# Schematic.net
KiCad netlist of a schematic drawn in Altium Designer
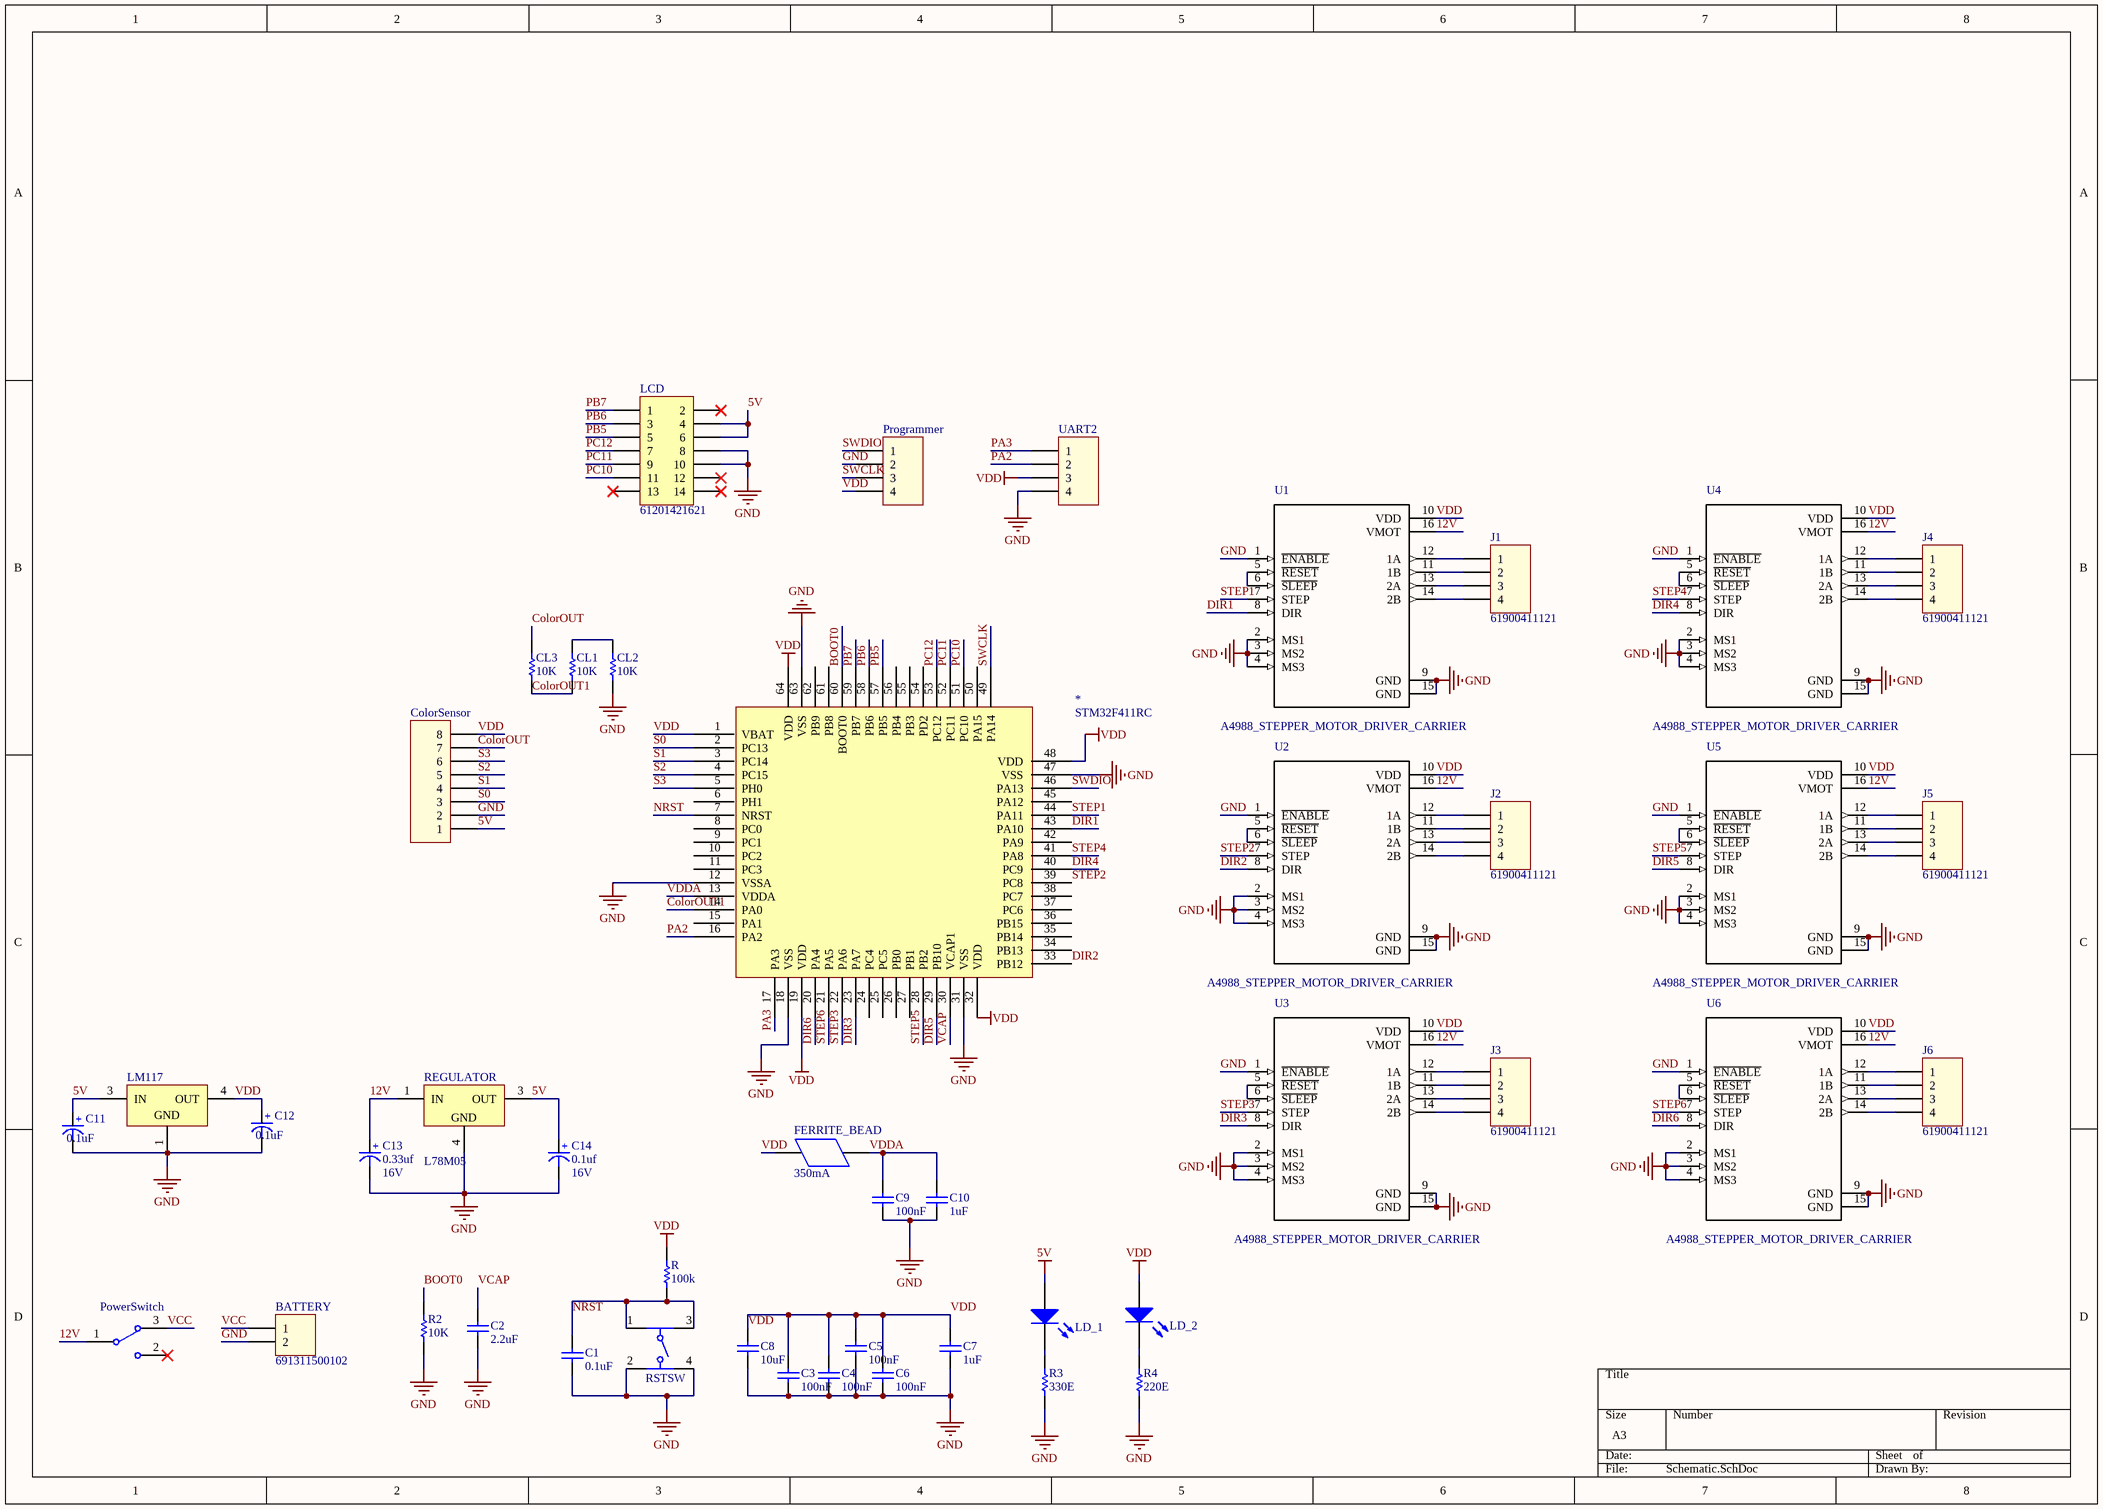
[diagram p0: Schematic.SchDoc]

(export (version "E")
  (design (tool "Eeschema 10.0.6"))
  (components
    (comp (ref "*")
      (value "STM32F411RC")
      (footprint "STM32F411RC_")
      (libsource (lib "STM32F411RCT6_LQFP64_NEW") (part "STM32F411RC"))
    )
    (comp (ref "BATTERY")
      (value "691311500102")
      (footprint "691311500102")
      (description "WR-TBL Serie 311 - 5.08 mm Close Vertical PCB Header, 02p")
      (fields (field (name "PUBLISHER") "Wurth Elektronik"))
      (libsource (lib "Phoenix - Female 5.08mm") (part "691311500102"))
    )
    (comp (ref "C1")
      (value "0.1uF")
      (footprint "CAPC3413X12N")
      (description "CAP 0805")
      (fields (field (name "DESIGNER") "Abbas Basereh"))
      (libsource (lib "Altium") (part "CAP SMD 0805"))
    )
    (comp (ref "C2")
      (value "2.2uF")
      (footprint "CAPC3413X12N")
      (description "CAP 0805")
      (fields (field (name "DESIGNER") "Abbas Basereh"))
      (libsource (lib "Altium") (part "CAP SMD 0805"))
    )
    (comp (ref "C3")
      (value "100nF")
      (footprint "CAPC3413X12N")
      (description "CAP 0805")
      (fields (field (name "DESIGNER") "Abbas Basereh"))
      (libsource (lib "Altium") (part "CAP SMD 0805"))
    )
    (comp (ref "C4")
      (value "100nF")
      (footprint "CAPC3413X12N")
      (description "CAP 0805")
      (fields (field (name "DESIGNER") "Abbas Basereh"))
      (libsource (lib "Altium") (part "CAP SMD 0805"))
    )
    (comp (ref "C5")
      (value "100nF")
      (footprint "CAPC3413X12N")
      (description "CAP 0805")
      (fields (field (name "DESIGNER") "Abbas Basereh"))
      (libsource (lib "Altium") (part "CAP SMD 0805"))
    )
    (comp (ref "C6")
      (value "100nF")
      (footprint "CAPC3413X12N")
      (description "CAP 0805")
      (fields (field (name "DESIGNER") "Abbas Basereh"))
      (libsource (lib "Altium") (part "CAP SMD 0805"))
    )
    (comp (ref "C7")
      (value "1uF")
      (footprint "CAPC3413X12N")
      (description "CAP 0805")
      (fields (field (name "DESIGNER") "Abbas Basereh"))
      (libsource (lib "Altium") (part "CAP SMD 0805"))
    )
    (comp (ref "C8")
      (value "10uF")
      (footprint "CAPC3413X12N")
      (description "CAP 0805")
      (fields (field (name "DESIGNER") "Abbas Basereh"))
      (libsource (lib "Altium") (part "CAP SMD 0805"))
    )
    (comp (ref "C9")
      (value "100nF")
      (footprint "CAPC3413X12N")
      (description "CAP 0805")
      (fields (field (name "DESIGNER") "Abbas Basereh"))
      (libsource (lib "Altium") (part "CAP SMD 0805"))
    )
    (comp (ref "C10")
      (value "1uF")
      (footprint "CAPC3413X12N")
      (description "CAP 0805")
      (fields (field (name "DESIGNER") "Abbas Basereh"))
      (libsource (lib "Altium") (part "CAP SMD 0805"))
    )
    (comp (ref "C11")
      (value "0.1uF")
      (footprint "cap 00")
      (description "Polar Capacitor")
      (fields (field (name "DESIGNER") "Eng. Saeid Jorablo") (field (name "PUBLISHER") "SJ Unlimited"))
      (libsource (lib "Passives") (part "CAP_Polar"))
    )
    (comp (ref "C12")
      (value "0.1uF")
      (footprint "cap 00")
      (description "Polar Capacitor")
      (fields (field (name "DESIGNER") "Eng. Saeid Jorablo") (field (name "PUBLISHER") "SJ Unlimited"))
      (libsource (lib "Passives") (part "CAP_Polar"))
    )
    (comp (ref "C13")
      (value "0.33uf")
      (footprint "cap 01")
      (description "Polar Capacitor")
      (fields
        (field (name "VOLTAGE") "16V")
        (field (name "DESIGNER") "Eng. Saeid Jorablo")
        (field (name "PUBLISHER") "SJ Unlimited")
      )
      (libsource (lib "Passives") (part "CAP_Polar"))
    )
    (comp (ref "C14")
      (value "0.1uf")
      (footprint "cap 01")
      (description "Polar Capacitor")
      (fields
        (field (name "VOLTAGE") "16V")
        (field (name "DESIGNER") "Eng. Saeid Jorablo")
        (field (name "PUBLISHER") "SJ Unlimited")
      )
      (libsource (lib "Passives") (part "CAP_Polar"))
    )
    (comp (ref "CL1")
      (value "10K")
      (footprint "RES0805")
      (description "TOTAL SMD RESISTOR PACK")
      (fields (field (name "DESIGNER") "Abbas Basereh"))
      (libsource (lib "Altium") (part "RES SMD PACKAGE"))
    )
    (comp (ref "CL2")
      (value "10K")
      (footprint "RES0805")
      (description "TOTAL SMD RESISTOR PACK")
      (fields (field (name "DESIGNER") "Abbas Basereh"))
      (libsource (lib "Altium") (part "RES SMD PACKAGE"))
    )
    (comp (ref "CL3")
      (value "10K")
      (footprint "RES0805")
      (description "TOTAL SMD RESISTOR PACK")
      (fields (field (name "DESIGNER") "Abbas Basereh"))
      (libsource (lib "Altium") (part "RES SMD PACKAGE"))
    )
    (comp (ref "ColorSensor")
      (value "~")
      (footprint "61900811121")
      (description "WR-WTB 2.54mm Male Locking Header, 8p")
      (fields (field (name "PART NUMBER") "61900811121") (field (name "PUBLISHER") "Wurth Elektronik"))
      (libsource (lib "Relimate") (part "61900811121"))
    )
    (comp (ref "FERRITE_BEAD")
      (value "350mA")
      (footprint "PassiveComponents:0805 (2012) Capacitor")
      (description "Ferrite Beads")
      (libsource (lib "PassiveComponents") (part "Ferrite Beads"))
    )
    (comp (ref "J1")
      (value "61900411121")
      (footprint "61900411121")
      (description "WR-WTB 2.54mm Male Locking Header, 4p")
      (fields (field (name "PUBLISHER") "Wurth Elektronik"))
      (libsource (lib "Relimate") (part "61900411121"))
    )
    (comp (ref "J2")
      (value "61900411121")
      (footprint "61900411121")
      (description "WR-WTB 2.54mm Male Locking Header, 4p")
      (fields (field (name "PUBLISHER") "Wurth Elektronik"))
      (libsource (lib "Relimate") (part "61900411121"))
    )
    (comp (ref "J3")
      (value "61900411121")
      (footprint "61900411121")
      (description "WR-WTB 2.54mm Male Locking Header, 4p")
      (fields (field (name "PUBLISHER") "Wurth Elektronik"))
      (libsource (lib "Relimate") (part "61900411121"))
    )
    (comp (ref "J4")
      (value "61900411121")
      (footprint "61900411121")
      (description "WR-WTB 2.54mm Male Locking Header, 4p")
      (fields (field (name "PUBLISHER") "Wurth Elektronik"))
      (libsource (lib "Relimate") (part "61900411121"))
    )
    (comp (ref "J5")
      (value "61900411121")
      (footprint "61900411121")
      (description "WR-WTB 2.54mm Male Locking Header, 4p")
      (fields (field (name "PUBLISHER") "Wurth Elektronik"))
      (libsource (lib "Relimate") (part "61900411121"))
    )
    (comp (ref "J6")
      (value "61900411121")
      (footprint "61900411121")
      (description "WR-WTB 2.54mm Male Locking Header, 4p")
      (fields (field (name "PUBLISHER") "Wurth Elektronik"))
      (libsource (lib "Relimate") (part "61900411121"))
    )
    (comp (ref "LCD")
      (value "61201421621")
      (footprint "61201421621")
      (description "WR-BHD 2.54mm Male Box Header")
      (fields (field (name "MANUFACTURER") "Wurth Elektronik") (field (name "CREATED BY") "Baojun Chen"))
      (libsource (lib "FRC Base") (part "61201421621"))
    )
    (comp (ref "LD_1")
      (value "SMD 1206 LED")
      (footprint "LED-3mm")
      (description "Typical LED")
      (libsource (lib "AbbasBasereh09365731239") (part "LED 3mm"))
    )
    (comp (ref "LD_2")
      (value "SMD 1206 LED")
      (footprint "LED-3mm")
      (description "Typical LED")
      (libsource (lib "AbbasBasereh09365731239") (part "LED 3mm"))
    )
    (comp (ref "LM117")
      (value "~")
      (footprint "SOT223_N")
      (description "x.x Volt, 800mA Low-Dropout Linear Regulator, 3-pin TO-252")
      (fields
        (field (name "PARTNUMBER") "LM1117DT-3.3")
        (field (name "MANUFACTURER") "National Semiconductor")
      )
      (libsource (lib "Altium") (part "LM1117DT-x.x"))
    )
    (comp (ref "PowerSwitch")
      (value "450301014042")
      (footprint "450301014042")
      (description "WS-SLTV 10x2.5 mm THT")
      (fields (field (name "PUBLISHER") "Wurth Elektronik"))
      (libsource (lib "Switch - SlideSwitch RED") (part "450301014042"))
    )
    (comp (ref "Programmer")
      (value "~")
      (footprint "61900411121")
      (description "WR-WTB 2.54mm Male Locking Header, 4p")
      (fields (field (name "PART NUMBER") "61900411121") (field (name "PUBLISHER") "Wurth Elektronik"))
      (libsource (lib "Relimate") (part "61900411121"))
    )
    (comp (ref "R")
      (value "100k")
      (footprint "RES0805")
      (description "TOTAL SMD RESISTOR PACK")
      (fields (field (name "DESIGNER") "Abbas Basereh"))
      (libsource (lib "Altium") (part "RES SMD PACKAGE"))
    )
    (comp (ref "R2")
      (value "10K")
      (footprint "RES0805")
      (description "TOTAL SMD RESISTOR PACK")
      (fields (field (name "DESIGNER") "Abbas Basereh"))
      (libsource (lib "Altium") (part "RES SMD PACKAGE"))
    )
    (comp (ref "R3")
      (value "330E")
      (footprint "RES0805")
      (description "TOTAL SMD RESISTOR PACK")
      (fields (field (name "DESIGNER") "Abbas Basereh"))
      (libsource (lib "Altium") (part "RES SMD PACKAGE"))
    )
    (comp (ref "R4")
      (value "220E")
      (footprint "RES0805")
      (description "TOTAL SMD RESISTOR PACK")
      (fields (field (name "DESIGNER") "Abbas Basereh"))
      (libsource (lib "Altium") (part "RES SMD PACKAGE"))
    )
    (comp (ref "REGULATOR")
      (value "L78M05")
      (footprint "TO-252")
      (description "Precision 500mA Regulator")
      (libsource (lib "Altium") (part "L78M05"))
    )
    (comp (ref "RSTSW")
      (value "430156050736")
      (footprint "4301x60507x6_6x6x5")
      (description "WS-TATV 6x6mm Tact Switch, THT version")
      (fields (field (name "PUBLISHER") "Wurth Elektronik"))
      (libsource (lib "Switch - Tactile") (part "430156050736"))
    )
    (comp (ref "U1")
      (value "A4988_STEPPER_MOTOR_DRIVER_CARRIER")
      (footprint "*MODULE_A4988_STEPPER_MOTOR_DRIVER_CARRIER")
      (description "Stepper Motor Driver")
      (fields (field (name "MF") "Pololu") (field (name "MP") "A4988 STEPPER MOTOR DRIVER CARRIER"))
      (libsource (lib "A4988_STEPPER_MOTOR_DRIVER_CARRIER") (part "A4988_STEPPER_MOTOR_DRIVER_CARRIER"))
    )
    (comp (ref "U2")
      (value "A4988_STEPPER_MOTOR_DRIVER_CARRIER")
      (footprint "*MODULE_A4988_STEPPER_MOTOR_DRIVER_CARRIER")
      (description "Stepper Motor Driver")
      (fields (field (name "MF") "Pololu") (field (name "MP") "A4988 STEPPER MOTOR DRIVER CARRIER"))
      (libsource (lib "A4988_STEPPER_MOTOR_DRIVER_CARRIER") (part "A4988_STEPPER_MOTOR_DRIVER_CARRIER"))
    )
    (comp (ref "U3")
      (value "A4988_STEPPER_MOTOR_DRIVER_CARRIER")
      (footprint "*MODULE_A4988_STEPPER_MOTOR_DRIVER_CARRIER")
      (description "Stepper Motor Driver")
      (fields (field (name "MF") "Pololu") (field (name "MP") "A4988 STEPPER MOTOR DRIVER CARRIER"))
      (libsource (lib "A4988_STEPPER_MOTOR_DRIVER_CARRIER") (part "A4988_STEPPER_MOTOR_DRIVER_CARRIER"))
    )
    (comp (ref "U4")
      (value "A4988_STEPPER_MOTOR_DRIVER_CARRIER")
      (footprint "*MODULE_A4988_STEPPER_MOTOR_DRIVER_CARRIER")
      (description "Stepper Motor Driver")
      (fields (field (name "MF") "Pololu") (field (name "MP") "A4988 STEPPER MOTOR DRIVER CARRIER"))
      (libsource (lib "A4988_STEPPER_MOTOR_DRIVER_CARRIER") (part "A4988_STEPPER_MOTOR_DRIVER_CARRIER"))
    )
    (comp (ref "U5")
      (value "A4988_STEPPER_MOTOR_DRIVER_CARRIER")
      (footprint "*MODULE_A4988_STEPPER_MOTOR_DRIVER_CARRIER")
      (description "Stepper Motor Driver")
      (fields (field (name "MF") "Pololu") (field (name "MP") "A4988 STEPPER MOTOR DRIVER CARRIER"))
      (libsource (lib "A4988_STEPPER_MOTOR_DRIVER_CARRIER") (part "A4988_STEPPER_MOTOR_DRIVER_CARRIER"))
    )
    (comp (ref "U6")
      (value "A4988_STEPPER_MOTOR_DRIVER_CARRIER")
      (footprint "*MODULE_A4988_STEPPER_MOTOR_DRIVER_CARRIER")
      (description "Stepper Motor Driver")
      (fields (field (name "MF") "Pololu") (field (name "MP") "A4988 STEPPER MOTOR DRIVER CARRIER"))
      (libsource (lib "A4988_STEPPER_MOTOR_DRIVER_CARRIER") (part "A4988_STEPPER_MOTOR_DRIVER_CARRIER"))
    )
    (comp (ref "UART2")
      (value "~")
      (footprint "61900411121")
      (description "WR-WTB 2.54mm Male Locking Header, 4p")
      (fields (field (name "PART NUMBER") "61900411121") (field (name "PUBLISHER") "Wurth Elektronik"))
      (libsource (lib "Relimate") (part "61900411121"))
    )
  )
  (nets
    (net (code "1") (name "/12V") (class "Default")
      (node (ref "C13") (pin "1") (pinfunction "+_1") (pintype "passive"))
      (node (ref "PowerSwitch") (pin "1") (pinfunction "COM_1") (pintype "passive"))
      (node (ref "REGULATOR") (pin "1") (pinfunction "IN_1") (pintype "power_in"))
      (node (ref "U1") (pin "16") (pinfunction "VMOT_16") (pintype "power_in"))
      (node (ref "U2") (pin "16") (pinfunction "VMOT_16") (pintype "power_in"))
      (node (ref "U3") (pin "16") (pinfunction "VMOT_16") (pintype "power_in"))
      (node (ref "U4") (pin "16") (pinfunction "VMOT_16") (pintype "power_in"))
      (node (ref "U5") (pin "16") (pinfunction "VMOT_16") (pintype "power_in"))
      (node (ref "U6") (pin "16") (pinfunction "VMOT_16") (pintype "power_in"))
    )
    (net (code "2") (name "/BOOT0") (class "Default")
      (node (ref "*") (pin "60") (pinfunction "BOOT0_60") (pintype "passive"))
      (node (ref "R2") (pin "2") (pinfunction "2_2") (pintype "passive"))
    )
    (net (code "3") (name "/ColorOUT") (class "Default")
      (node (ref "CL3") (pin "2") (pinfunction "2_2") (pintype "passive"))
      (node (ref "ColorSensor") (pin "7") (pinfunction "7_7") (pintype "passive"))
    )
    (net (code "4") (name "/ColorOUT1") (class "Default")
      (node (ref "*") (pin "14") (pinfunction "PA0_14") (pintype "passive"))
      (node (ref "CL1") (pin "1") (pinfunction "1_1") (pintype "passive"))
      (node (ref "CL3") (pin "1") (pinfunction "1_1") (pintype "passive"))
    )
    (net (code "5") (name "/DIR1") (class "Default")
      (node (ref "*") (pin "43") (pinfunction "PA10_43") (pintype "passive"))
      (node (ref "U1") (pin "8") (pinfunction "DIR_8") (pintype "input"))
    )
    (net (code "6") (name "/DIR2") (class "Default")
      (node (ref "*") (pin "33") (pinfunction "PB12_33") (pintype "passive"))
      (node (ref "U2") (pin "8") (pinfunction "DIR_8") (pintype "input"))
    )
    (net (code "7") (name "/DIR3") (class "Default")
      (node (ref "*") (pin "23") (pinfunction "PA7_23") (pintype "passive"))
      (node (ref "U3") (pin "8") (pinfunction "DIR_8") (pintype "input"))
    )
    (net (code "8") (name "/DIR4") (class "Default")
      (node (ref "*") (pin "40") (pinfunction "PC9_40") (pintype "passive"))
      (node (ref "U4") (pin "8") (pinfunction "DIR_8") (pintype "input"))
    )
    (net (code "9") (name "/DIR5") (class "Default")
      (node (ref "*") (pin "29") (pinfunction "PB10_29") (pintype "passive"))
      (node (ref "U5") (pin "8") (pinfunction "DIR_8") (pintype "input"))
    )
    (net (code "10") (name "/DIR6") (class "Default")
      (node (ref "*") (pin "20") (pinfunction "PA4_20") (pintype "passive"))
      (node (ref "U6") (pin "8") (pinfunction "DIR_8") (pintype "input"))
    )
    (net (code "11") (name "/NRST") (class "Default")
      (node (ref "*") (pin "7") (pinfunction "NRST_7") (pintype "passive"))
      (node (ref "C1") (pin "1") (pinfunction "1_1") (pintype "passive"))
      (node (ref "R") (pin "1") (pinfunction "1_1") (pintype "passive"))
      (node (ref "RSTSW") (pin "1") (pinfunction "1_1") (pintype "passive"))
      (node (ref "RSTSW") (pin "3") (pinfunction "3_3") (pintype "passive"))
    )
    (net (code "12") (name "/PA2") (class "Default")
      (node (ref "*") (pin "16") (pinfunction "PA2_16") (pintype "passive"))
      (node (ref "UART2") (pin "2") (pinfunction "2_2") (pintype "passive"))
    )
    (net (code "13") (name "/PA3") (class "Default")
      (node (ref "*") (pin "17") (pinfunction "PA3_17") (pintype "passive"))
      (node (ref "UART2") (pin "1") (pinfunction "1_1") (pintype "passive"))
    )
    (net (code "14") (name "/PB5") (class "Default")
      (node (ref "*") (pin "57") (pinfunction "PB5_57") (pintype "passive"))
      (node (ref "LCD") (pin "5") (pinfunction "5_5") (pintype "passive"))
    )
    (net (code "15") (name "/PB6") (class "Default")
      (node (ref "*") (pin "58") (pinfunction "PB6_58") (pintype "passive"))
      (node (ref "LCD") (pin "3") (pinfunction "3_3") (pintype "passive"))
    )
    (net (code "16") (name "/PB7") (class "Default")
      (node (ref "*") (pin "59") (pinfunction "PB7_59") (pintype "passive"))
      (node (ref "LCD") (pin "1") (pinfunction "1_1") (pintype "passive"))
    )
    (net (code "17") (name "/PC10") (class "Default")
      (node (ref "*") (pin "51") (pinfunction "PC10_51") (pintype "passive"))
      (node (ref "LCD") (pin "11") (pinfunction "11_11") (pintype "passive"))
    )
    (net (code "18") (name "/PC11") (class "Default")
      (node (ref "*") (pin "52") (pinfunction "PC11_52") (pintype "passive"))
      (node (ref "LCD") (pin "9") (pinfunction "9_9") (pintype "passive"))
    )
    (net (code "19") (name "/PC12") (class "Default")
      (node (ref "*") (pin "53") (pinfunction "PC12_53") (pintype "passive"))
      (node (ref "LCD") (pin "7") (pinfunction "7_7") (pintype "passive"))
    )
    (net (code "20") (name "/S0") (class "Default")
      (node (ref "*") (pin "2") (pinfunction "PC13_2") (pintype "passive"))
      (node (ref "ColorSensor") (pin "3") (pinfunction "3_3") (pintype "passive"))
    )
    (net (code "21") (name "/S1") (class "Default")
      (node (ref "*") (pin "3") (pinfunction "PC14_3") (pintype "passive"))
      (node (ref "ColorSensor") (pin "4") (pinfunction "4_4") (pintype "passive"))
    )
    (net (code "22") (name "/S2") (class "Default")
      (node (ref "*") (pin "4") (pinfunction "PC15_4") (pintype "passive"))
      (node (ref "ColorSensor") (pin "5") (pinfunction "5_5") (pintype "passive"))
    )
    (net (code "23") (name "/S3") (class "Default")
      (node (ref "*") (pin "5") (pinfunction "PH0_5") (pintype "passive"))
      (node (ref "ColorSensor") (pin "6") (pinfunction "6_6") (pintype "passive"))
    )
    (net (code "24") (name "/STEP1") (class "Default")
      (node (ref "*") (pin "44") (pinfunction "PA11_44") (pintype "passive"))
      (node (ref "U1") (pin "7") (pinfunction "STEP_7") (pintype "input"))
    )
    (net (code "25") (name "/STEP2") (class "Default")
      (node (ref "*") (pin "39") (pinfunction "PC8_39") (pintype "passive"))
      (node (ref "U2") (pin "7") (pinfunction "STEP_7") (pintype "input"))
    )
    (net (code "26") (name "/STEP3") (class "Default")
      (node (ref "*") (pin "22") (pinfunction "PA6_22") (pintype "passive"))
      (node (ref "U3") (pin "7") (pinfunction "STEP_7") (pintype "input"))
    )
    (net (code "27") (name "/STEP4") (class "Default")
      (node (ref "*") (pin "41") (pinfunction "PA8_41") (pintype "passive"))
      (node (ref "U4") (pin "7") (pinfunction "STEP_7") (pintype "input"))
    )
    (net (code "28") (name "/STEP5") (class "Default")
      (node (ref "*") (pin "28") (pinfunction "PB2_28") (pintype "passive"))
      (node (ref "U5") (pin "7") (pinfunction "STEP_7") (pintype "input"))
    )
    (net (code "29") (name "/STEP6") (class "Default")
      (node (ref "*") (pin "21") (pinfunction "PA5_21") (pintype "passive"))
      (node (ref "U6") (pin "7") (pinfunction "STEP_7") (pintype "input"))
    )
    (net (code "30") (name "/SWCLK") (class "Default")
      (node (ref "*") (pin "49") (pinfunction "PA14_49") (pintype "passive"))
      (node (ref "Programmer") (pin "3") (pinfunction "3_3") (pintype "passive"))
    )
    (net (code "31") (name "/SWDIO") (class "Default")
      (node (ref "*") (pin "46") (pinfunction "PA13_46") (pintype "passive"))
      (node (ref "Programmer") (pin "1") (pinfunction "1_1") (pintype "passive"))
    )
    (net (code "32") (name "/VCAP") (class "Default")
      (node (ref "*") (pin "30") (pinfunction "VCAP1_30") (pintype "passive"))
      (node (ref "C2") (pin "1") (pinfunction "1_1") (pintype "passive"))
    )
    (net (code "33") (name "/VCC") (class "Default")
      (node (ref "BATTERY") (pin "1") (pinfunction "1_1") (pintype "passive"))
      (node (ref "PowerSwitch") (pin "3") (pinfunction "3_3") (pintype "passive"))
    )
    (net (code "34") (name "/VDDA") (class "Default")
      (node (ref "*") (pin "13") (pinfunction "VDDA_13") (pintype "passive"))
      (node (ref "C10") (pin "2") (pinfunction "2_2") (pintype "passive"))
      (node (ref "C9") (pin "2") (pinfunction "2_2") (pintype "passive"))
      (node (ref "FERRITE_BEAD") (pin "1") (pinfunction "1_1") (pintype "passive"))
    )
    (net (code "35") (name "5V") (class "Default")
      (node (ref "C11") (pin "1") (pinfunction "+_1") (pintype "passive"))
      (node (ref "C14") (pin "1") (pinfunction "+_1") (pintype "passive"))
      (node (ref "ColorSensor") (pin "1") (pinfunction "1_1") (pintype "passive"))
      (node (ref "LCD") (pin "4") (pinfunction "4_4") (pintype "passive"))
      (node (ref "LCD") (pin "6") (pinfunction "6_6") (pintype "passive"))
      (node (ref "LD_1") (pin "1") (pinfunction "A_1") (pintype "passive"))
      (node (ref "LM117") (pin "3") (pinfunction "IN_3") (pintype "power_in"))
      (node (ref "REGULATOR") (pin "3") (pinfunction "OUT_3") (pintype "power_in"))
    )
    (net (code "36") (name "GND") (class "Default")
      (node (ref "*") (pin "12") (pinfunction "VSSA_12") (pintype "passive"))
      (node (ref "*") (pin "18") (pinfunction "VSS_18") (pintype "passive"))
      (node (ref "*") (pin "31") (pinfunction "VSS_31") (pintype "passive"))
      (node (ref "*") (pin "47") (pinfunction "VSS_47") (pintype "passive"))
      (node (ref "*") (pin "63") (pinfunction "VSS_63") (pintype "passive"))
      (node (ref "BATTERY") (pin "2") (pinfunction "2_2") (pintype "passive"))
      (node (ref "C1") (pin "2") (pinfunction "2_2") (pintype "passive"))
      (node (ref "C10") (pin "1") (pinfunction "1_1") (pintype "passive"))
      (node (ref "C11") (pin "2") (pinfunction "-_2") (pintype "passive"))
      (node (ref "C12") (pin "2") (pinfunction "-_2") (pintype "passive"))
      (node (ref "C13") (pin "2") (pinfunction "-_2") (pintype "passive"))
      (node (ref "C14") (pin "2") (pinfunction "-_2") (pintype "passive"))
      (node (ref "C2") (pin "2") (pinfunction "2_2") (pintype "passive"))
      (node (ref "C3") (pin "1") (pinfunction "1_1") (pintype "passive"))
      (node (ref "C4") (pin "1") (pinfunction "1_1") (pintype "passive"))
      (node (ref "C5") (pin "1") (pinfunction "1_1") (pintype "passive"))
      (node (ref "C6") (pin "1") (pinfunction "1_1") (pintype "passive"))
      (node (ref "C7") (pin "1") (pinfunction "1_1") (pintype "passive"))
      (node (ref "C8") (pin "1") (pinfunction "1_1") (pintype "passive"))
      (node (ref "C9") (pin "1") (pinfunction "1_1") (pintype "passive"))
      (node (ref "CL2") (pin "1") (pinfunction "1_1") (pintype "passive"))
      (node (ref "ColorSensor") (pin "2") (pinfunction "2_2") (pintype "passive"))
      (node (ref "LCD") (pin "10") (pinfunction "10_10") (pintype "passive"))
      (node (ref "LCD") (pin "8") (pinfunction "8_8") (pintype "passive"))
      (node (ref "LM117") (pin "1") (pinfunction "GND_1") (pintype "power_in"))
      (node (ref "Programmer") (pin "2") (pinfunction "2_2") (pintype "passive"))
      (node (ref "R2") (pin "1") (pinfunction "1_1") (pintype "passive"))
      (node (ref "R3") (pin "1") (pinfunction "1_1") (pintype "passive"))
      (node (ref "R4") (pin "1") (pinfunction "1_1") (pintype "passive"))
      (node (ref "REGULATOR") (pin "4") (pinfunction "GND_4") (pintype "power_in"))
      (node (ref "RSTSW") (pin "2") (pinfunction "2_2") (pintype "passive"))
      (node (ref "RSTSW") (pin "4") (pinfunction "4_4") (pintype "passive"))
      (node (ref "U1") (pin "1") (pinfunction "~{ENABLE}_1") (pintype "input"))
      (node (ref "U1") (pin "15") (pinfunction "GND_15") (pintype "power_in"))
      (node (ref "U1") (pin "2") (pinfunction "MS1_2") (pintype "input"))
      (node (ref "U1") (pin "3") (pinfunction "MS2_3") (pintype "input"))
      (node (ref "U1") (pin "4") (pinfunction "MS3_4") (pintype "input"))
      (node (ref "U1") (pin "9") (pinfunction "GND_9") (pintype "power_in"))
      (node (ref "U2") (pin "1") (pinfunction "~{ENABLE}_1") (pintype "input"))
      (node (ref "U2") (pin "15") (pinfunction "GND_15") (pintype "power_in"))
      (node (ref "U2") (pin "2") (pinfunction "MS1_2") (pintype "input"))
      (node (ref "U2") (pin "3") (pinfunction "MS2_3") (pintype "input"))
      (node (ref "U2") (pin "4") (pinfunction "MS3_4") (pintype "input"))
      (node (ref "U2") (pin "9") (pinfunction "GND_9") (pintype "power_in"))
      (node (ref "U3") (pin "1") (pinfunction "~{ENABLE}_1") (pintype "input"))
      (node (ref "U3") (pin "15") (pinfunction "GND_15") (pintype "power_in"))
      (node (ref "U3") (pin "2") (pinfunction "MS1_2") (pintype "input"))
      (node (ref "U3") (pin "3") (pinfunction "MS2_3") (pintype "input"))
      (node (ref "U3") (pin "4") (pinfunction "MS3_4") (pintype "input"))
      (node (ref "U3") (pin "9") (pinfunction "GND_9") (pintype "power_in"))
      (node (ref "U4") (pin "1") (pinfunction "~{ENABLE}_1") (pintype "input"))
      (node (ref "U4") (pin "15") (pinfunction "GND_15") (pintype "power_in"))
      (node (ref "U4") (pin "2") (pinfunction "MS1_2") (pintype "input"))
      (node (ref "U4") (pin "3") (pinfunction "MS2_3") (pintype "input"))
      (node (ref "U4") (pin "4") (pinfunction "MS3_4") (pintype "input"))
      (node (ref "U4") (pin "9") (pinfunction "GND_9") (pintype "power_in"))
      (node (ref "U5") (pin "1") (pinfunction "~{ENABLE}_1") (pintype "input"))
      (node (ref "U5") (pin "15") (pinfunction "GND_15") (pintype "power_in"))
      (node (ref "U5") (pin "2") (pinfunction "MS1_2") (pintype "input"))
      (node (ref "U5") (pin "3") (pinfunction "MS2_3") (pintype "input"))
      (node (ref "U5") (pin "4") (pinfunction "MS3_4") (pintype "input"))
      (node (ref "U5") (pin "9") (pinfunction "GND_9") (pintype "power_in"))
      (node (ref "U6") (pin "1") (pinfunction "~{ENABLE}_1") (pintype "input"))
      (node (ref "U6") (pin "15") (pinfunction "GND_15") (pintype "power_in"))
      (node (ref "U6") (pin "2") (pinfunction "MS1_2") (pintype "input"))
      (node (ref "U6") (pin "3") (pinfunction "MS2_3") (pintype "input"))
      (node (ref "U6") (pin "4") (pinfunction "MS3_4") (pintype "input"))
      (node (ref "U6") (pin "9") (pinfunction "GND_9") (pintype "power_in"))
      (node (ref "UART2") (pin "4") (pinfunction "4_4") (pintype "passive"))
    )
    (net (code "37") (name "Net-(CL1-Pad2)") (class "Default")
      (node (ref "CL1") (pin "2") (pinfunction "2_2") (pintype "passive"))
      (node (ref "CL2") (pin "2") (pinfunction "2_2") (pintype "passive"))
    )
    (net (code "38") (name "Net-(LD_1-K)") (class "Default")
      (node (ref "LD_1") (pin "2") (pinfunction "K_2") (pintype "passive"))
      (node (ref "R3") (pin "2") (pinfunction "2_2") (pintype "passive"))
    )
    (net (code "39") (name "Net-(LD_2-K)") (class "Default")
      (node (ref "LD_2") (pin "2") (pinfunction "K_2") (pintype "passive"))
      (node (ref "R4") (pin "2") (pinfunction "2_2") (pintype "passive"))
    )
    (net (code "40") (name "Net-(U1-1A)") (class "Default")
      (node (ref "J1") (pin "1") (pinfunction "1_1") (pintype "passive"))
      (node (ref "U1") (pin "12") (pinfunction "1A_12") (pintype "output"))
    )
    (net (code "41") (name "Net-(U1-1B)") (class "Default")
      (node (ref "J1") (pin "2") (pinfunction "2_2") (pintype "passive"))
      (node (ref "U1") (pin "11") (pinfunction "1B_11") (pintype "output"))
    )
    (net (code "42") (name "Net-(U1-2A)") (class "Default")
      (node (ref "J1") (pin "3") (pinfunction "3_3") (pintype "passive"))
      (node (ref "U1") (pin "13") (pinfunction "2A_13") (pintype "output"))
    )
    (net (code "43") (name "Net-(U1-2B)") (class "Default")
      (node (ref "J1") (pin "4") (pinfunction "4_4") (pintype "passive"))
      (node (ref "U1") (pin "14") (pinfunction "2B_14") (pintype "output"))
    )
    (net (code "44") (name "Net-(U1-~{RESET})") (class "Default")
      (node (ref "U1") (pin "5") (pinfunction "~{RESET}_5") (pintype "input"))
      (node (ref "U1") (pin "6") (pinfunction "~{SLEEP}_6") (pintype "input"))
    )
    (net (code "45") (name "Net-(U2-1A)") (class "Default")
      (node (ref "J2") (pin "1") (pinfunction "1_1") (pintype "passive"))
      (node (ref "U2") (pin "12") (pinfunction "1A_12") (pintype "output"))
    )
    (net (code "46") (name "Net-(U2-1B)") (class "Default")
      (node (ref "J2") (pin "2") (pinfunction "2_2") (pintype "passive"))
      (node (ref "U2") (pin "11") (pinfunction "1B_11") (pintype "output"))
    )
    (net (code "47") (name "Net-(U2-2A)") (class "Default")
      (node (ref "J2") (pin "3") (pinfunction "3_3") (pintype "passive"))
      (node (ref "U2") (pin "13") (pinfunction "2A_13") (pintype "output"))
    )
    (net (code "48") (name "Net-(U2-2B)") (class "Default")
      (node (ref "J2") (pin "4") (pinfunction "4_4") (pintype "passive"))
      (node (ref "U2") (pin "14") (pinfunction "2B_14") (pintype "output"))
    )
    (net (code "49") (name "Net-(U2-~{RESET})") (class "Default")
      (node (ref "U2") (pin "5") (pinfunction "~{RESET}_5") (pintype "input"))
      (node (ref "U2") (pin "6") (pinfunction "~{SLEEP}_6") (pintype "input"))
    )
    (net (code "50") (name "Net-(U3-1A)") (class "Default")
      (node (ref "J3") (pin "1") (pinfunction "1_1") (pintype "passive"))
      (node (ref "U3") (pin "12") (pinfunction "1A_12") (pintype "output"))
    )
    (net (code "51") (name "Net-(U3-1B)") (class "Default")
      (node (ref "J3") (pin "2") (pinfunction "2_2") (pintype "passive"))
      (node (ref "U3") (pin "11") (pinfunction "1B_11") (pintype "output"))
    )
    (net (code "52") (name "Net-(U3-2A)") (class "Default")
      (node (ref "J3") (pin "3") (pinfunction "3_3") (pintype "passive"))
      (node (ref "U3") (pin "13") (pinfunction "2A_13") (pintype "output"))
    )
    (net (code "53") (name "Net-(U3-2B)") (class "Default")
      (node (ref "J3") (pin "4") (pinfunction "4_4") (pintype "passive"))
      (node (ref "U3") (pin "14") (pinfunction "2B_14") (pintype "output"))
    )
    (net (code "54") (name "Net-(U3-~{RESET})") (class "Default")
      (node (ref "U3") (pin "5") (pinfunction "~{RESET}_5") (pintype "input"))
      (node (ref "U3") (pin "6") (pinfunction "~{SLEEP}_6") (pintype "input"))
    )
    (net (code "55") (name "Net-(U4-1A)") (class "Default")
      (node (ref "J4") (pin "1") (pinfunction "1_1") (pintype "passive"))
      (node (ref "U4") (pin "12") (pinfunction "1A_12") (pintype "output"))
    )
    (net (code "56") (name "Net-(U4-1B)") (class "Default")
      (node (ref "J4") (pin "2") (pinfunction "2_2") (pintype "passive"))
      (node (ref "U4") (pin "11") (pinfunction "1B_11") (pintype "output"))
    )
    (net (code "57") (name "Net-(U4-2A)") (class "Default")
      (node (ref "J4") (pin "3") (pinfunction "3_3") (pintype "passive"))
      (node (ref "U4") (pin "13") (pinfunction "2A_13") (pintype "output"))
    )
    (net (code "58") (name "Net-(U4-2B)") (class "Default")
      (node (ref "J4") (pin "4") (pinfunction "4_4") (pintype "passive"))
      (node (ref "U4") (pin "14") (pinfunction "2B_14") (pintype "output"))
    )
    (net (code "59") (name "Net-(U4-~{RESET})") (class "Default")
      (node (ref "U4") (pin "5") (pinfunction "~{RESET}_5") (pintype "input"))
      (node (ref "U4") (pin "6") (pinfunction "~{SLEEP}_6") (pintype "input"))
    )
    (net (code "60") (name "Net-(U5-1A)") (class "Default")
      (node (ref "J5") (pin "1") (pinfunction "1_1") (pintype "passive"))
      (node (ref "U5") (pin "12") (pinfunction "1A_12") (pintype "output"))
    )
    (net (code "61") (name "Net-(U5-1B)") (class "Default")
      (node (ref "J5") (pin "2") (pinfunction "2_2") (pintype "passive"))
      (node (ref "U5") (pin "11") (pinfunction "1B_11") (pintype "output"))
    )
    (net (code "62") (name "Net-(U5-2A)") (class "Default")
      (node (ref "J5") (pin "3") (pinfunction "3_3") (pintype "passive"))
      (node (ref "U5") (pin "13") (pinfunction "2A_13") (pintype "output"))
    )
    (net (code "63") (name "Net-(U5-2B)") (class "Default")
      (node (ref "J5") (pin "4") (pinfunction "4_4") (pintype "passive"))
      (node (ref "U5") (pin "14") (pinfunction "2B_14") (pintype "output"))
    )
    (net (code "64") (name "Net-(U5-~{RESET})") (class "Default")
      (node (ref "U5") (pin "5") (pinfunction "~{RESET}_5") (pintype "input"))
      (node (ref "U5") (pin "6") (pinfunction "~{SLEEP}_6") (pintype "input"))
    )
    (net (code "65") (name "Net-(U6-1A)") (class "Default")
      (node (ref "J6") (pin "1") (pinfunction "1_1") (pintype "passive"))
      (node (ref "U6") (pin "12") (pinfunction "1A_12") (pintype "output"))
    )
    (net (code "66") (name "Net-(U6-1B)") (class "Default")
      (node (ref "J6") (pin "2") (pinfunction "2_2") (pintype "passive"))
      (node (ref "U6") (pin "11") (pinfunction "1B_11") (pintype "output"))
    )
    (net (code "67") (name "Net-(U6-2A)") (class "Default")
      (node (ref "J6") (pin "3") (pinfunction "3_3") (pintype "passive"))
      (node (ref "U6") (pin "13") (pinfunction "2A_13") (pintype "output"))
    )
    (net (code "68") (name "Net-(U6-2B)") (class "Default")
      (node (ref "J6") (pin "4") (pinfunction "4_4") (pintype "passive"))
      (node (ref "U6") (pin "14") (pinfunction "2B_14") (pintype "output"))
    )
    (net (code "69") (name "Net-(U6-~{RESET})") (class "Default")
      (node (ref "U6") (pin "5") (pinfunction "~{RESET}_5") (pintype "input"))
      (node (ref "U6") (pin "6") (pinfunction "~{SLEEP}_6") (pintype "input"))
    )
    (net (code "70") (name "VDD") (class "Default")
      (node (ref "*") (pin "1") (pinfunction "VBAT_1") (pintype "passive"))
      (node (ref "*") (pin "19") (pinfunction "VDD_19") (pintype "passive"))
      (node (ref "*") (pin "32") (pinfunction "VDD_32") (pintype "passive"))
      (node (ref "*") (pin "48") (pinfunction "VDD_48") (pintype "passive"))
      (node (ref "*") (pin "64") (pinfunction "VDD_64") (pintype "passive"))
      (node (ref "C12") (pin "1") (pinfunction "+_1") (pintype "passive"))
      (node (ref "C3") (pin "2") (pinfunction "2_2") (pintype "passive"))
      (node (ref "C4") (pin "2") (pinfunction "2_2") (pintype "passive"))
      (node (ref "C5") (pin "2") (pinfunction "2_2") (pintype "passive"))
      (node (ref "C6") (pin "2") (pinfunction "2_2") (pintype "passive"))
      (node (ref "C7") (pin "2") (pinfunction "2_2") (pintype "passive"))
      (node (ref "C8") (pin "2") (pinfunction "2_2") (pintype "passive"))
      (node (ref "ColorSensor") (pin "8") (pinfunction "8_8") (pintype "passive"))
      (node (ref "FERRITE_BEAD") (pin "2") (pinfunction "2_2") (pintype "passive"))
      (node (ref "LD_2") (pin "1") (pinfunction "A_1") (pintype "passive"))
      (node (ref "LM117") (pin "4") (pinfunction "OUT_4") (pintype "power_in"))
      (node (ref "Programmer") (pin "4") (pinfunction "4_4") (pintype "passive"))
      (node (ref "R") (pin "2") (pinfunction "2_2") (pintype "passive"))
      (node (ref "U1") (pin "10") (pinfunction "VDD_10") (pintype "power_in"))
      (node (ref "U2") (pin "10") (pinfunction "VDD_10") (pintype "power_in"))
      (node (ref "U3") (pin "10") (pinfunction "VDD_10") (pintype "power_in"))
      (node (ref "U4") (pin "10") (pinfunction "VDD_10") (pintype "power_in"))
      (node (ref "U5") (pin "10") (pinfunction "VDD_10") (pintype "power_in"))
      (node (ref "U6") (pin "10") (pinfunction "VDD_10") (pintype "power_in"))
      (node (ref "UART2") (pin "3") (pinfunction "3_3") (pintype "passive"))
    )
    (net (code "71") (name "unconnected-(*-PA1-Pad15)") (class "Default")
      (node (ref "*") (pin "15") (pinfunction "PA1_15") (pintype "passive"))
    )
    (net (code "72") (name "unconnected-(*-PA9-Pad42)") (class "Default")
      (node (ref "*") (pin "42") (pinfunction "PA9_42") (pintype "passive"))
    )
    (net (code "73") (name "unconnected-(*-PA12-Pad45)") (class "Default")
      (node (ref "*") (pin "45") (pinfunction "PA12_45") (pintype "passive"))
    )
    (net (code "74") (name "unconnected-(*-PA15-Pad50)") (class "Default")
      (node (ref "*") (pin "50") (pinfunction "PA15_50") (pintype "passive"))
    )
    (net (code "75") (name "unconnected-(*-PB0-Pad26)") (class "Default")
      (node (ref "*") (pin "26") (pinfunction "PB0_26") (pintype "passive"))
    )
    (net (code "76") (name "unconnected-(*-PB1-Pad27)") (class "Default")
      (node (ref "*") (pin "27") (pinfunction "PB1_27") (pintype "passive"))
    )
    (net (code "77") (name "unconnected-(*-PB3-Pad55)") (class "Default")
      (node (ref "*") (pin "55") (pinfunction "PB3_55") (pintype "passive"))
    )
    (net (code "78") (name "unconnected-(*-PB4-Pad56)") (class "Default")
      (node (ref "*") (pin "56") (pinfunction "PB4_56") (pintype "passive"))
    )
    (net (code "79") (name "unconnected-(*-PB8-Pad61)") (class "Default")
      (node (ref "*") (pin "61") (pinfunction "PB8_61") (pintype "passive"))
    )
    (net (code "80") (name "unconnected-(*-PB9-Pad62)") (class "Default")
      (node (ref "*") (pin "62") (pinfunction "PB9_62") (pintype "passive"))
    )
    (net (code "81") (name "unconnected-(*-PB13-Pad34)") (class "Default")
      (node (ref "*") (pin "34") (pinfunction "PB13_34") (pintype "passive"))
    )
    (net (code "82") (name "unconnected-(*-PB14-Pad35)") (class "Default")
      (node (ref "*") (pin "35") (pinfunction "PB14_35") (pintype "passive"))
    )
    (net (code "83") (name "unconnected-(*-PB15-Pad36)") (class "Default")
      (node (ref "*") (pin "36") (pinfunction "PB15_36") (pintype "passive"))
    )
    (net (code "84") (name "unconnected-(*-PC0-Pad8)") (class "Default")
      (node (ref "*") (pin "8") (pinfunction "PC0_8") (pintype "passive"))
    )
    (net (code "85") (name "unconnected-(*-PC1-Pad9)") (class "Default")
      (node (ref "*") (pin "9") (pinfunction "PC1_9") (pintype "passive"))
    )
    (net (code "86") (name "unconnected-(*-PC2-Pad10)") (class "Default")
      (node (ref "*") (pin "10") (pinfunction "PC2_10") (pintype "passive"))
    )
    (net (code "87") (name "unconnected-(*-PC3-Pad11)") (class "Default")
      (node (ref "*") (pin "11") (pinfunction "PC3_11") (pintype "passive"))
    )
    (net (code "88") (name "unconnected-(*-PC4-Pad24)") (class "Default")
      (node (ref "*") (pin "24") (pinfunction "PC4_24") (pintype "passive"))
    )
    (net (code "89") (name "unconnected-(*-PC5-Pad25)") (class "Default")
      (node (ref "*") (pin "25") (pinfunction "PC5_25") (pintype "passive"))
    )
    (net (code "90") (name "unconnected-(*-PC6-Pad37)") (class "Default")
      (node (ref "*") (pin "37") (pinfunction "PC6_37") (pintype "passive"))
    )
    (net (code "91") (name "unconnected-(*-PC7-Pad38)") (class "Default")
      (node (ref "*") (pin "38") (pinfunction "PC7_38") (pintype "passive"))
    )
    (net (code "92") (name "unconnected-(*-PD2-Pad54)") (class "Default")
      (node (ref "*") (pin "54") (pinfunction "PD2_54") (pintype "passive"))
    )
    (net (code "93") (name "unconnected-(*-PH1-Pad6)") (class "Default")
      (node (ref "*") (pin "6") (pinfunction "PH1_6") (pintype "passive"))
    )
    (net (code "94") (name "unconnected-(LCD-Pad2)") (class "Default")
      (node (ref "LCD") (pin "2") (pinfunction "2_2") (pintype "passive+no_connect"))
    )
    (net (code "95") (name "unconnected-(LCD-Pad12)") (class "Default")
      (node (ref "LCD") (pin "12") (pinfunction "12_12") (pintype "passive+no_connect"))
    )
    (net (code "96") (name "unconnected-(LCD-Pad13)") (class "Default")
      (node (ref "LCD") (pin "13") (pinfunction "13_13") (pintype "passive+no_connect"))
    )
    (net (code "97") (name "unconnected-(LCD-Pad14)") (class "Default")
      (node (ref "LCD") (pin "14") (pinfunction "14_14") (pintype "passive+no_connect"))
    )
    (net (code "98") (name "unconnected-(PowerSwitch-Pad2)") (class "Default")
      (node (ref "PowerSwitch") (pin "2") (pinfunction "2_2") (pintype "passive+no_connect"))
    )
  )
)
